# DM1097_CM4_HS.net
KiCad netlist of a schematic drawn in Altium Designer
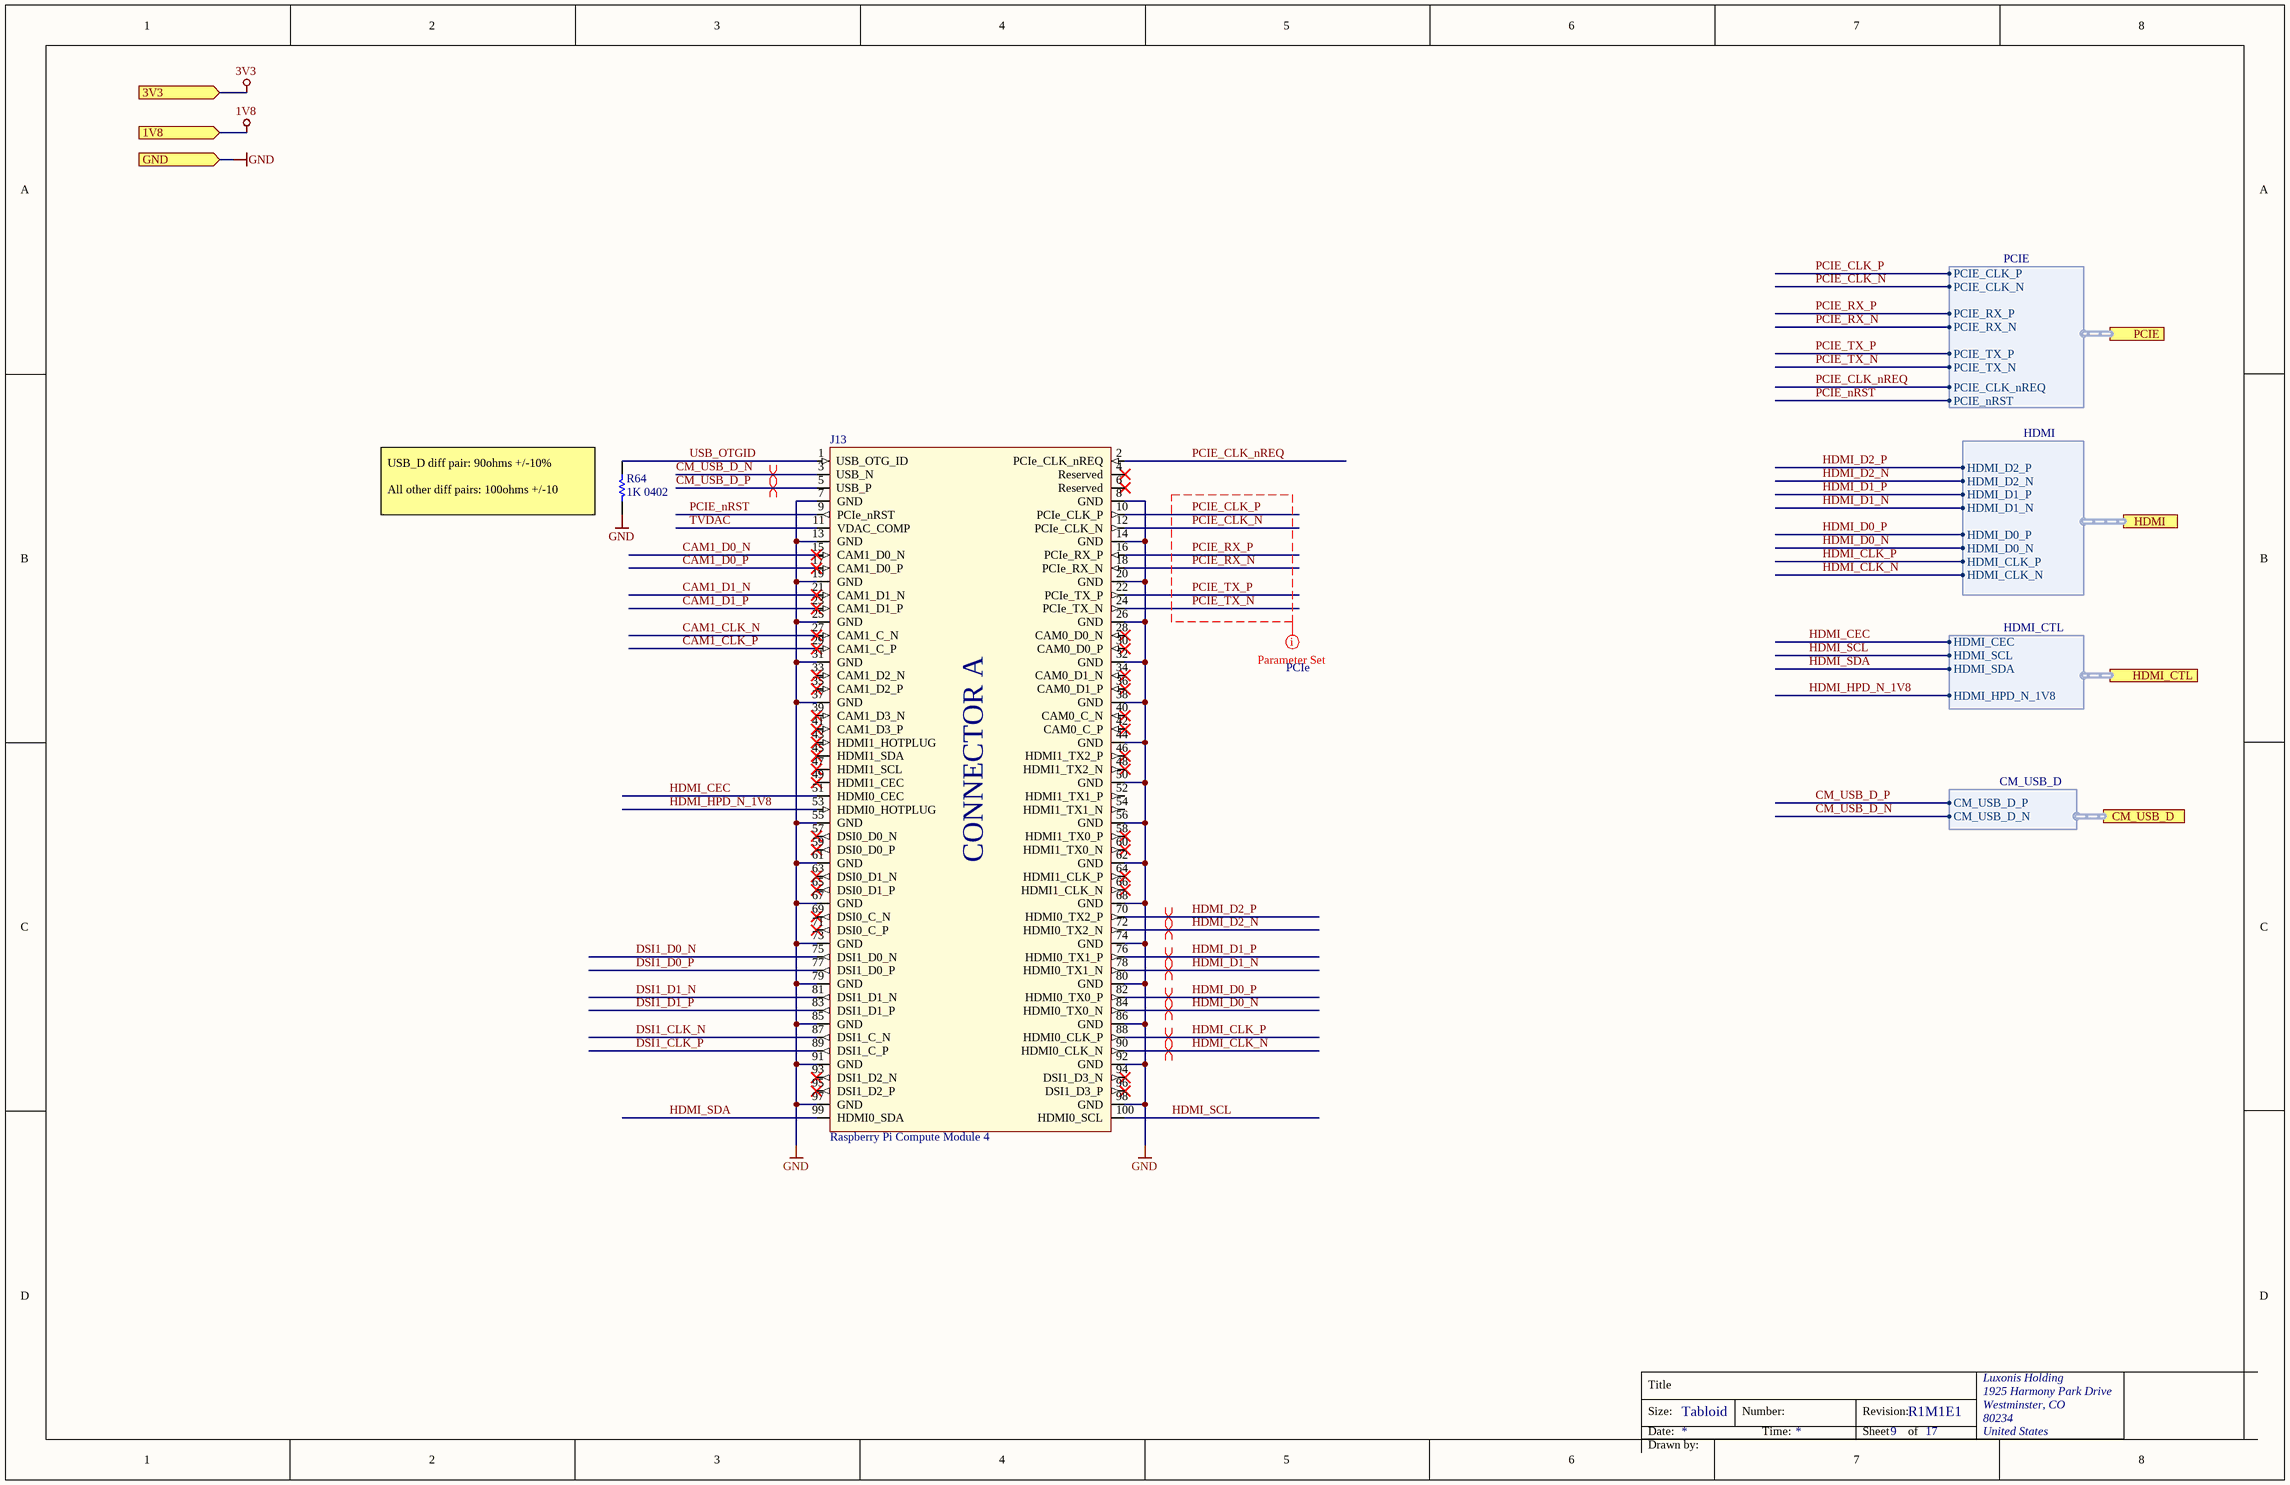
[diagram p0: DM1097_CM4_HS.SchDoc]

(export (version "E")
  (design (tool "Eeschema 10.0.6"))
  (components
    (comp (ref "J13")
      (value "Raspberry Pi Compute Module 4")
      (footprint "CM4-Connector-A")
      (description "Raspberry Pi Compute Module 4 Hirose connector A")
      (libsource (lib "DM1097_R1M1E1") (part "CM4_CONNECTOR_A"))
    )
    (comp (ref "R64")
      (value "1K 0402")
      (footprint "RES_Altium_Vault_Generic:RESC0402(1005)_N")
      (fields (field (name "TOLERANCE") "1%"))
      (libsource (lib "LuxonisMaster") (part "RC0402FR-071KL"))
    )
  )
  (nets
    (net (code "5") (name "/CAM1_CLK_N") (class "Default")
      (node (ref "J13") (pin "27") (pinfunction "CAM1_C_N_27") (pintype "input+no_connect"))
    )
    (net (code "6") (name "/CAM1_CLK_P") (class "Default")
      (node (ref "J13") (pin "29") (pinfunction "CAM1_C_P_29") (pintype "input+no_connect"))
    )
    (net (code "7") (name "/CAM1_D0_N") (class "Default")
      (node (ref "J13") (pin "15") (pinfunction "CAM1_D0_N_15") (pintype "input+no_connect"))
    )
    (net (code "8") (name "/CAM1_D0_P") (class "Default")
      (node (ref "J13") (pin "17") (pinfunction "CAM1_D0_P_17") (pintype "input+no_connect"))
    )
    (net (code "9") (name "/CAM1_D1_N") (class "Default")
      (node (ref "J13") (pin "21") (pinfunction "CAM1_D1_N_21") (pintype "input+no_connect"))
    )
    (net (code "10") (name "/CAM1_D1_P") (class "Default")
      (node (ref "J13") (pin "23") (pinfunction "CAM1_D1_P_23") (pintype "input+no_connect"))
    )
    (net (code "11") (name "/CM_USB_D_N") (class "Default")
      (node (ref "J13") (pin "3") (pinfunction "USB_N_3") (pintype "passive"))
    )
    (net (code "12") (name "/CM_USB_D_P") (class "Default")
      (node (ref "J13") (pin "5") (pinfunction "USB_P_5") (pintype "passive"))
    )
    (net (code "13") (name "/DSI1_CLK_N") (class "Default")
      (node (ref "J13") (pin "87") (pinfunction "DSI1_C_N_87") (pintype "output"))
    )
    (net (code "14") (name "/DSI1_CLK_P") (class "Default")
      (node (ref "J13") (pin "89") (pinfunction "DSI1_C_P_89") (pintype "output"))
    )
    (net (code "15") (name "/DSI1_D0_N") (class "Default")
      (node (ref "J13") (pin "75") (pinfunction "DSI1_D0_N_75") (pintype "output"))
    )
    (net (code "16") (name "/DSI1_D0_P") (class "Default")
      (node (ref "J13") (pin "77") (pinfunction "DSI1_D0_P_77") (pintype "output"))
    )
    (net (code "17") (name "/DSI1_D1_N") (class "Default")
      (node (ref "J13") (pin "81") (pinfunction "DSI1_D1_N_81") (pintype "output"))
    )
    (net (code "18") (name "/DSI1_D1_P") (class "Default")
      (node (ref "J13") (pin "83") (pinfunction "DSI1_D1_P_83") (pintype "output"))
    )
    (net (code "19") (name "/HDMI_CEC") (class "Default")
      (node (ref "J13") (pin "51") (pinfunction "HDMI0_CEC_51") (pintype "open_collector"))
    )
    (net (code "20") (name "/HDMI_CLK_N") (class "Default")
      (node (ref "J13") (pin "90") (pinfunction "HDMI0_CLK_N_90") (pintype "output"))
    )
    (net (code "21") (name "/HDMI_CLK_P") (class "Default")
      (node (ref "J13") (pin "88") (pinfunction "HDMI0_CLK_P_88") (pintype "output"))
    )
    (net (code "22") (name "/HDMI_D0_N") (class "Default")
      (node (ref "J13") (pin "84") (pinfunction "HDMI0_TX0_N_84") (pintype "output"))
    )
    (net (code "23") (name "/HDMI_D0_P") (class "Default")
      (node (ref "J13") (pin "82") (pinfunction "HDMI0_TX0_P_82") (pintype "output"))
    )
    (net (code "24") (name "/HDMI_D1_N") (class "Default")
      (node (ref "J13") (pin "78") (pinfunction "HDMI0_TX1_N_78") (pintype "output"))
    )
    (net (code "25") (name "/HDMI_D1_P") (class "Default")
      (node (ref "J13") (pin "76") (pinfunction "HDMI0_TX1_P_76") (pintype "output"))
    )
    (net (code "26") (name "/HDMI_D2_N") (class "Default")
      (node (ref "J13") (pin "72") (pinfunction "HDMI0_TX2_N_72") (pintype "output"))
    )
    (net (code "27") (name "/HDMI_D2_P") (class "Default")
      (node (ref "J13") (pin "70") (pinfunction "HDMI0_TX2_P_70") (pintype "output"))
    )
    (net (code "28") (name "/HDMI_HPD_N_1V8") (class "Default")
      (node (ref "J13") (pin "53") (pinfunction "HDMI0_HOTPLUG_53") (pintype "input"))
    )
    (net (code "29") (name "/HDMI_SCL") (class "Default")
      (node (ref "J13") (pin "100") (pinfunction "HDMI0_SCL_100") (pintype "open_collector"))
    )
    (net (code "30") (name "/HDMI_SDA") (class "Default")
      (node (ref "J13") (pin "99") (pinfunction "HDMI0_SDA_99") (pintype "bidirectional"))
    )
    (net (code "31") (name "/PCIE_CLK_N") (class "Default")
      (node (ref "J13") (pin "12") (pinfunction "PCIe_CLK_N_12") (pintype "output"))
    )
    (net (code "32") (name "/PCIE_CLK_P") (class "Default")
      (node (ref "J13") (pin "10") (pinfunction "PCIe_CLK_P_10") (pintype "output"))
    )
    (net (code "33") (name "/PCIE_CLK_nREQ") (class "Default")
      (node (ref "J13") (pin "2") (pinfunction "PCIe_CLK_nREQ_2") (pintype "input"))
    )
    (net (code "34") (name "/PCIE_RX_N") (class "Default")
      (node (ref "J13") (pin "18") (pinfunction "PCIe_RX_N_18") (pintype "input"))
    )
    (net (code "35") (name "/PCIE_RX_P") (class "Default")
      (node (ref "J13") (pin "16") (pinfunction "PCIe_RX_P_16") (pintype "input"))
    )
    (net (code "36") (name "/PCIE_TX_N") (class "Default")
      (node (ref "J13") (pin "24") (pinfunction "PCIe_TX_N_24") (pintype "output"))
    )
    (net (code "37") (name "/PCIE_TX_P") (class "Default")
      (node (ref "J13") (pin "22") (pinfunction "PCIe_TX_P_22") (pintype "output"))
    )
    (net (code "38") (name "/PCIE_nRST") (class "Default")
      (node (ref "J13") (pin "9") (pinfunction "PCIe_nRST_9") (pintype "output"))
    )
    (net (code "39") (name "/TVDAC") (class "Default")
      (node (ref "J13") (pin "11") (pinfunction "VDAC_COMP_11") (pintype "passive"))
    )
    (net (code "40") (name "/USB_OTGID") (class "Default")
      (node (ref "J13") (pin "1") (pinfunction "USB_OTG_ID_1") (pintype "input"))
      (node (ref "R64") (pin "2") (pinfunction "2_2") (pintype "passive"))
    )
    (net (code "47") (name "GND") (class "Default")
      (node (ref "J13") (pin "13") (pinfunction "GND_13") (pintype "power_in"))
      (node (ref "J13") (pin "14") (pinfunction "GND_14") (pintype "power_in"))
      (node (ref "J13") (pin "19") (pinfunction "GND_19") (pintype "power_in"))
      (node (ref "J13") (pin "20") (pinfunction "GND_20") (pintype "power_in"))
      (node (ref "J13") (pin "25") (pinfunction "GND_25") (pintype "power_in"))
      (node (ref "J13") (pin "26") (pinfunction "GND_26") (pintype "power_in"))
      (node (ref "J13") (pin "31") (pinfunction "GND_31") (pintype "power_in"))
      (node (ref "J13") (pin "32") (pinfunction "GND_32") (pintype "power_in"))
      (node (ref "J13") (pin "37") (pinfunction "GND_37") (pintype "power_in"))
      (node (ref "J13") (pin "38") (pinfunction "GND_38") (pintype "power_in"))
      (node (ref "J13") (pin "44") (pinfunction "GND_44") (pintype "power_in"))
      (node (ref "J13") (pin "50") (pinfunction "GND_50") (pintype "power_in"))
      (node (ref "J13") (pin "55") (pinfunction "GND_55") (pintype "power_in"))
      (node (ref "J13") (pin "56") (pinfunction "GND_56") (pintype "power_in"))
      (node (ref "J13") (pin "61") (pinfunction "GND_61") (pintype "power_in"))
      (node (ref "J13") (pin "62") (pinfunction "GND_62") (pintype "power_in"))
      (node (ref "J13") (pin "67") (pinfunction "GND_67") (pintype "power_in"))
      (node (ref "J13") (pin "68") (pinfunction "GND_68") (pintype "power_in"))
      (node (ref "J13") (pin "7") (pinfunction "GND_7") (pintype "power_in"))
      (node (ref "J13") (pin "73") (pinfunction "GND_73") (pintype "power_in"))
      (node (ref "J13") (pin "74") (pinfunction "GND_74") (pintype "power_in"))
      (node (ref "J13") (pin "79") (pinfunction "GND_79") (pintype "power_in"))
      (node (ref "J13") (pin "8") (pinfunction "GND_8") (pintype "power_in"))
      (node (ref "J13") (pin "80") (pinfunction "GND_80") (pintype "power_in"))
      (node (ref "J13") (pin "85") (pinfunction "GND_85") (pintype "power_in"))
      (node (ref "J13") (pin "86") (pinfunction "GND_86") (pintype "power_in"))
      (node (ref "J13") (pin "91") (pinfunction "GND_91") (pintype "power_in"))
      (node (ref "J13") (pin "92") (pinfunction "GND_92") (pintype "power_in"))
      (node (ref "J13") (pin "97") (pinfunction "GND_97") (pintype "power_in"))
      (node (ref "J13") (pin "98") (pinfunction "GND_98") (pintype "power_in"))
      (node (ref "R64") (pin "1") (pinfunction "1_1") (pintype "passive"))
    )
    (net (code "48") (name "unconnected-(J13-CAM0_C_N-Pad40)") (class "Default")
      (node (ref "J13") (pin "40") (pinfunction "CAM0_C_N_40") (pintype "input+no_connect"))
    )
    (net (code "49") (name "unconnected-(J13-CAM0_C_P-Pad42)") (class "Default")
      (node (ref "J13") (pin "42") (pinfunction "CAM0_C_P_42") (pintype "input+no_connect"))
    )
    (net (code "50") (name "unconnected-(J13-CAM0_D0_N-Pad28)") (class "Default")
      (node (ref "J13") (pin "28") (pinfunction "CAM0_D0_N_28") (pintype "input+no_connect"))
    )
    (net (code "51") (name "unconnected-(J13-CAM0_D0_P-Pad30)") (class "Default")
      (node (ref "J13") (pin "30") (pinfunction "CAM0_D0_P_30") (pintype "input+no_connect"))
    )
    (net (code "52") (name "unconnected-(J13-CAM0_D1_N-Pad34)") (class "Default")
      (node (ref "J13") (pin "34") (pinfunction "CAM0_D1_N_34") (pintype "input+no_connect"))
    )
    (net (code "53") (name "unconnected-(J13-CAM0_D1_P-Pad36)") (class "Default")
      (node (ref "J13") (pin "36") (pinfunction "CAM0_D1_P_36") (pintype "input+no_connect"))
    )
    (net (code "54") (name "unconnected-(J13-CAM1_D2_N-Pad33)") (class "Default")
      (node (ref "J13") (pin "33") (pinfunction "CAM1_D2_N_33") (pintype "input+no_connect"))
    )
    (net (code "55") (name "unconnected-(J13-CAM1_D2_P-Pad35)") (class "Default")
      (node (ref "J13") (pin "35") (pinfunction "CAM1_D2_P_35") (pintype "input+no_connect"))
    )
    (net (code "56") (name "unconnected-(J13-CAM1_D3_N-Pad39)") (class "Default")
      (node (ref "J13") (pin "39") (pinfunction "CAM1_D3_N_39") (pintype "input+no_connect"))
    )
    (net (code "57") (name "unconnected-(J13-CAM1_D3_P-Pad41)") (class "Default")
      (node (ref "J13") (pin "41") (pinfunction "CAM1_D3_P_41") (pintype "input+no_connect"))
    )
    (net (code "58") (name "unconnected-(J13-DSI0_C_N-Pad69)") (class "Default")
      (node (ref "J13") (pin "69") (pinfunction "DSI0_C_N_69") (pintype "output+no_connect"))
    )
    (net (code "59") (name "unconnected-(J13-DSI0_C_P-Pad71)") (class "Default")
      (node (ref "J13") (pin "71") (pinfunction "DSI0_C_P_71") (pintype "output+no_connect"))
    )
    (net (code "60") (name "unconnected-(J13-DSI0_D0_N-Pad57)") (class "Default")
      (node (ref "J13") (pin "57") (pinfunction "DSI0_D0_N_57") (pintype "output+no_connect"))
    )
    (net (code "61") (name "unconnected-(J13-DSI0_D0_P-Pad59)") (class "Default")
      (node (ref "J13") (pin "59") (pinfunction "DSI0_D0_P_59") (pintype "output+no_connect"))
    )
    (net (code "62") (name "unconnected-(J13-DSI0_D1_N-Pad63)") (class "Default")
      (node (ref "J13") (pin "63") (pinfunction "DSI0_D1_N_63") (pintype "output+no_connect"))
    )
    (net (code "63") (name "unconnected-(J13-DSI0_D1_P-Pad65)") (class "Default")
      (node (ref "J13") (pin "65") (pinfunction "DSI0_D1_P_65") (pintype "output+no_connect"))
    )
    (net (code "64") (name "unconnected-(J13-DSI1_D2_N-Pad93)") (class "Default")
      (node (ref "J13") (pin "93") (pinfunction "DSI1_D2_N_93") (pintype "output+no_connect"))
    )
    (net (code "65") (name "unconnected-(J13-DSI1_D2_P-Pad95)") (class "Default")
      (node (ref "J13") (pin "95") (pinfunction "DSI1_D2_P_95") (pintype "output+no_connect"))
    )
    (net (code "66") (name "unconnected-(J13-DSI1_D3_N-Pad94)") (class "Default")
      (node (ref "J13") (pin "94") (pinfunction "DSI1_D3_N_94") (pintype "output+no_connect"))
    )
    (net (code "67") (name "unconnected-(J13-DSI1_D3_P-Pad96)") (class "Default")
      (node (ref "J13") (pin "96") (pinfunction "DSI1_D3_P_96") (pintype "output+no_connect"))
    )
    (net (code "68") (name "unconnected-(J13-HDMI1_CEC-Pad49)") (class "Default")
      (node (ref "J13") (pin "49") (pinfunction "HDMI1_CEC_49") (pintype "open_collector+no_connect"))
    )
    (net (code "69") (name "unconnected-(J13-HDMI1_CLK_N-Pad66)") (class "Default")
      (node (ref "J13") (pin "66") (pinfunction "HDMI1_CLK_N_66") (pintype "output+no_connect"))
    )
    (net (code "70") (name "unconnected-(J13-HDMI1_CLK_P-Pad64)") (class "Default")
      (node (ref "J13") (pin "64") (pinfunction "HDMI1_CLK_P_64") (pintype "output+no_connect"))
    )
    (net (code "71") (name "unconnected-(J13-HDMI1_HOTPLUG-Pad43)") (class "Default")
      (node (ref "J13") (pin "43") (pinfunction "HDMI1_HOTPLUG_43") (pintype "input+no_connect"))
    )
    (net (code "72") (name "unconnected-(J13-HDMI1_SCL-Pad47)") (class "Default")
      (node (ref "J13") (pin "47") (pinfunction "HDMI1_SCL_47") (pintype "open_collector+no_connect"))
    )
    (net (code "73") (name "unconnected-(J13-HDMI1_SDA-Pad45)") (class "Default")
      (node (ref "J13") (pin "45") (pinfunction "HDMI1_SDA_45") (pintype "bidirectional+no_connect"))
    )
    (net (code "74") (name "unconnected-(J13-HDMI1_TX0_N-Pad60)") (class "Default")
      (node (ref "J13") (pin "60") (pinfunction "HDMI1_TX0_N_60") (pintype "output+no_connect"))
    )
    (net (code "75") (name "unconnected-(J13-HDMI1_TX0_P-Pad58)") (class "Default")
      (node (ref "J13") (pin "58") (pinfunction "HDMI1_TX0_P_58") (pintype "output+no_connect"))
    )
    (net (code "76") (name "unconnected-(J13-HDMI1_TX1_N-Pad54)") (class "Default")
      (node (ref "J13") (pin "54") (pinfunction "HDMI1_TX1_N_54") (pintype "output"))
    )
    (net (code "77") (name "unconnected-(J13-HDMI1_TX1_P-Pad52)") (class "Default")
      (node (ref "J13") (pin "52") (pinfunction "HDMI1_TX1_P_52") (pintype "output"))
    )
    (net (code "78") (name "unconnected-(J13-HDMI1_TX2_N-Pad48)") (class "Default")
      (node (ref "J13") (pin "48") (pinfunction "HDMI1_TX2_N_48") (pintype "output+no_connect"))
    )
    (net (code "79") (name "unconnected-(J13-HDMI1_TX2_P-Pad46)") (class "Default")
      (node (ref "J13") (pin "46") (pinfunction "HDMI1_TX2_P_46") (pintype "output+no_connect"))
    )
    (net (code "80") (name "unconnected-(J13-Reserved-Pad4)") (class "Default")
      (node (ref "J13") (pin "4") (pinfunction "Reserved_4") (pintype "passive+no_connect"))
    )
    (net (code "81") (name "unconnected-(J13-Reserved-Pad6)") (class "Default")
      (node (ref "J13") (pin "6") (pinfunction "Reserved_6") (pintype "passive+no_connect"))
    )
  )
)
